# oled2.net
KiCad netlist of a schematic drawn in EAGLE
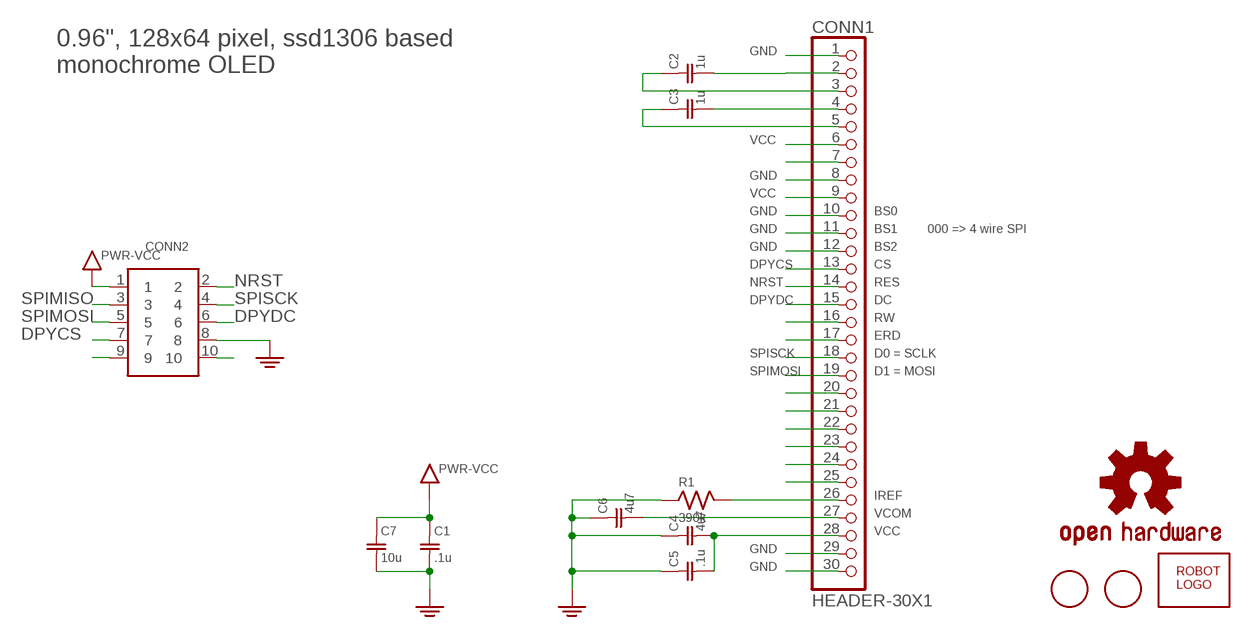
[diagram p0: schematic, sheet 1]

(export (version "E")
  (design (tool "Eeschema 10.0.6"))
  (components
    (comp (ref "C1")
      (value ".1u")
      (footprint "eagle-import:SMD0603")
      (libsource (lib "eagle-import") (part "C0603"))
    )
    (comp (ref "C2")
      (value "1u")
      (footprint "eagle-import:SMD0603")
      (libsource (lib "eagle-import") (part "C0603"))
    )
    (comp (ref "C3")
      (value "1u")
      (footprint "eagle-import:SMD0603")
      (libsource (lib "eagle-import") (part "C0603"))
    )
    (comp (ref "C4")
      (value "4u7")
      (footprint "eagle-import:SMD0603")
      (libsource (lib "eagle-import") (part "C0603"))
    )
    (comp (ref "C5")
      (value ".1u")
      (footprint "eagle-import:SMD0603")
      (libsource (lib "eagle-import") (part "C0603"))
    )
    (comp (ref "C6")
      (value "4u7")
      (footprint "eagle-import:SMD0603")
      (libsource (lib "eagle-import") (part "C0603"))
    )
    (comp (ref "C7")
      (value "10u")
      (footprint "eagle-import:SMD0603")
      (libsource (lib "eagle-import") (part "C0603"))
    )
    (comp (ref "CONN1")
      (value "HEADER-30X1")
      (footprint "eagle-import:HEADER-30X1-SMD7")
      (libsource (lib "eagle-import") (part "HEADER-30X1"))
    )
    (comp (ref "CONN2")
      (value "HEADER-5X2-PTH")
      (footprint "eagle-import:HEADER-5X2-PTH")
      (libsource (lib "eagle-import") (part "HEADER-5X2-PTH"))
    )
    (comp (ref "LOGO1")
      (value "OSHW-LOGOS")
      (footprint "eagle-import:OSHW-LOGO-S")
      (libsource (lib "eagle-import") (part "OSHW-LOGOS"))
    )
    (comp (ref "R1")
      (value "390k")
      (footprint "eagle-import:SMD0603")
      (libsource (lib "eagle-import") (part "R0603"))
    )
    (comp (ref "U$1")
      (value "FIDUCIAL")
      (footprint "eagle-import:FIDUCIAL_1MM")
      (libsource (lib "eagle-import") (part "FIDUCIAL"))
    )
    (comp (ref "U$2")
      (value "FIDUCIAL")
      (footprint "eagle-import:FIDUCIAL_1MM")
      (libsource (lib "eagle-import") (part "FIDUCIAL"))
    )
    (comp (ref "U$3")
      (value "ROBOTMAN-LOGO2")
      (footprint "eagle-import:ROBOTMAN-LOGO2")
      (libsource (lib "eagle-import") (part "ROBOTMAN-LOGO2"))
    )
  )
  (nets
    (net (code "1") (name "/DPYCS") (class "Default")
      (node (ref "CONN1") (pin "13") (pinfunction "13_13") (pintype "passive"))
      (node (ref "CONN2") (pin "7") (pinfunction "7_7") (pintype "passive"))
    )
    (net (code "2") (name "/DPYDC") (class "Default")
      (node (ref "CONN1") (pin "15") (pinfunction "15_15") (pintype "passive"))
      (node (ref "CONN2") (pin "6") (pinfunction "6_6") (pintype "passive"))
    )
    (net (code "3") (name "/NRST") (class "Default")
      (node (ref "CONN1") (pin "14") (pinfunction "14_14") (pintype "passive"))
      (node (ref "CONN2") (pin "2") (pinfunction "2_2") (pintype "passive"))
    )
    (net (code "4") (name "/SPIMISO") (class "Default")
      (node (ref "CONN2") (pin "3") (pinfunction "3_3") (pintype "passive"))
    )
    (net (code "5") (name "/SPIMOSI") (class "Default")
      (node (ref "CONN1") (pin "19") (pinfunction "19_19") (pintype "passive"))
      (node (ref "CONN2") (pin "5") (pinfunction "5_5") (pintype "passive"))
    )
    (net (code "6") (name "/SPISCK") (class "Default")
      (node (ref "CONN1") (pin "18") (pinfunction "18_18") (pintype "passive"))
      (node (ref "CONN2") (pin "4") (pinfunction "4_4") (pintype "passive"))
    )
    (net (code "7") (name "Net-(C2-P$1)") (class "Default")
      (node (ref "C2") (pin "1") (pinfunction "P$1_1") (pintype "passive"))
      (node (ref "CONN1") (pin "3") (pinfunction "3_3") (pintype "passive"))
    )
    (net (code "8") (name "Net-(C2-P$2)") (class "Default")
      (node (ref "C2") (pin "2") (pinfunction "P$2_2") (pintype "passive"))
      (node (ref "CONN1") (pin "2") (pinfunction "2_2") (pintype "passive"))
    )
    (net (code "9") (name "Net-(C3-P$1)") (class "Default")
      (node (ref "C3") (pin "1") (pinfunction "P$1_1") (pintype "passive"))
      (node (ref "CONN1") (pin "5") (pinfunction "5_5") (pintype "passive"))
    )
    (net (code "10") (name "Net-(C3-P$2)") (class "Default")
      (node (ref "C3") (pin "2") (pinfunction "P$2_2") (pintype "passive"))
      (node (ref "CONN1") (pin "4") (pinfunction "4_4") (pintype "passive"))
    )
    (net (code "11") (name "Net-(C4-P$2)") (class "Default")
      (node (ref "C4") (pin "2") (pinfunction "P$2_2") (pintype "passive"))
      (node (ref "C5") (pin "2") (pinfunction "P$2_2") (pintype "passive"))
      (node (ref "CONN1") (pin "28") (pinfunction "28_28") (pintype "passive"))
    )
    (net (code "12") (name "Net-(C6-P$2)") (class "Default")
      (node (ref "C6") (pin "2") (pinfunction "P$2_2") (pintype "passive"))
      (node (ref "CONN1") (pin "27") (pinfunction "27_27") (pintype "passive"))
    )
    (net (code "13") (name "Net-(R1-P$2)") (class "Default")
      (node (ref "CONN1") (pin "26") (pinfunction "26_26") (pintype "passive"))
      (node (ref "R1") (pin "2") (pinfunction "P$2_2") (pintype "passive"))
    )
    (net (code "14") (name "PWR-GND") (class "Default")
      (node (ref "C1") (pin "2") (pinfunction "P$2_2") (pintype "passive"))
      (node (ref "C4") (pin "1") (pinfunction "P$1_1") (pintype "passive"))
      (node (ref "C5") (pin "1") (pinfunction "P$1_1") (pintype "passive"))
      (node (ref "C6") (pin "1") (pinfunction "P$1_1") (pintype "passive"))
      (node (ref "C7") (pin "2") (pinfunction "P$2_2") (pintype "passive"))
      (node (ref "CONN1") (pin "1") (pinfunction "1_1") (pintype "passive"))
      (node (ref "CONN1") (pin "10") (pinfunction "10_10") (pintype "passive"))
      (node (ref "CONN1") (pin "11") (pinfunction "11_11") (pintype "passive"))
      (node (ref "CONN1") (pin "12") (pinfunction "12_12") (pintype "passive"))
      (node (ref "CONN1") (pin "29") (pinfunction "29_29") (pintype "passive"))
      (node (ref "CONN1") (pin "30") (pinfunction "30_30") (pintype "passive"))
      (node (ref "CONN1") (pin "8") (pinfunction "8_8") (pintype "passive"))
      (node (ref "CONN2") (pin "8") (pinfunction "8_8") (pintype "passive"))
      (node (ref "R1") (pin "1") (pinfunction "P$1_1") (pintype "passive"))
    )
    (net (code "15") (name "PWR-VCC") (class "Default")
      (node (ref "C1") (pin "1") (pinfunction "P$1_1") (pintype "passive"))
      (node (ref "C7") (pin "1") (pinfunction "P$1_1") (pintype "passive"))
      (node (ref "CONN1") (pin "6") (pinfunction "6_6") (pintype "passive"))
      (node (ref "CONN1") (pin "9") (pinfunction "9_9") (pintype "passive"))
      (node (ref "CONN2") (pin "1") (pinfunction "1_1") (pintype "passive"))
    )
    (net (code "16") (name "unconnected-(CONN1-Pad7)") (class "Default")
      (node (ref "CONN1") (pin "7") (pinfunction "7_7") (pintype "passive"))
    )
    (net (code "17") (name "unconnected-(CONN1-Pad16)") (class "Default")
      (node (ref "CONN1") (pin "16") (pinfunction "16_16") (pintype "passive"))
    )
    (net (code "18") (name "unconnected-(CONN1-Pad17)") (class "Default")
      (node (ref "CONN1") (pin "17") (pinfunction "17_17") (pintype "passive"))
    )
    (net (code "19") (name "unconnected-(CONN1-Pad20)") (class "Default")
      (node (ref "CONN1") (pin "20") (pinfunction "20_20") (pintype "passive"))
    )
    (net (code "20") (name "unconnected-(CONN1-Pad21)") (class "Default")
      (node (ref "CONN1") (pin "21") (pinfunction "21_21") (pintype "passive"))
    )
    (net (code "21") (name "unconnected-(CONN1-Pad22)") (class "Default")
      (node (ref "CONN1") (pin "22") (pinfunction "22_22") (pintype "passive"))
    )
    (net (code "22") (name "unconnected-(CONN1-Pad23)") (class "Default")
      (node (ref "CONN1") (pin "23") (pinfunction "23_23") (pintype "passive"))
    )
    (net (code "23") (name "unconnected-(CONN1-Pad24)") (class "Default")
      (node (ref "CONN1") (pin "24") (pinfunction "24_24") (pintype "passive"))
    )
    (net (code "24") (name "unconnected-(CONN1-Pad25)") (class "Default")
      (node (ref "CONN1") (pin "25") (pinfunction "25_25") (pintype "passive"))
    )
    (net (code "25") (name "unconnected-(CONN2-Pad9)") (class "Default")
      (node (ref "CONN2") (pin "9") (pinfunction "9_9") (pintype "passive"))
    )
    (net (code "26") (name "unconnected-(CONN2-Pad10)") (class "Default")
      (node (ref "CONN2") (pin "10") (pinfunction "10_10") (pintype "passive"))
    )
  )
)
